# Gimbal-Motor-PowerBoard.net
KiCad netlist of a schematic drawn in EAGLE
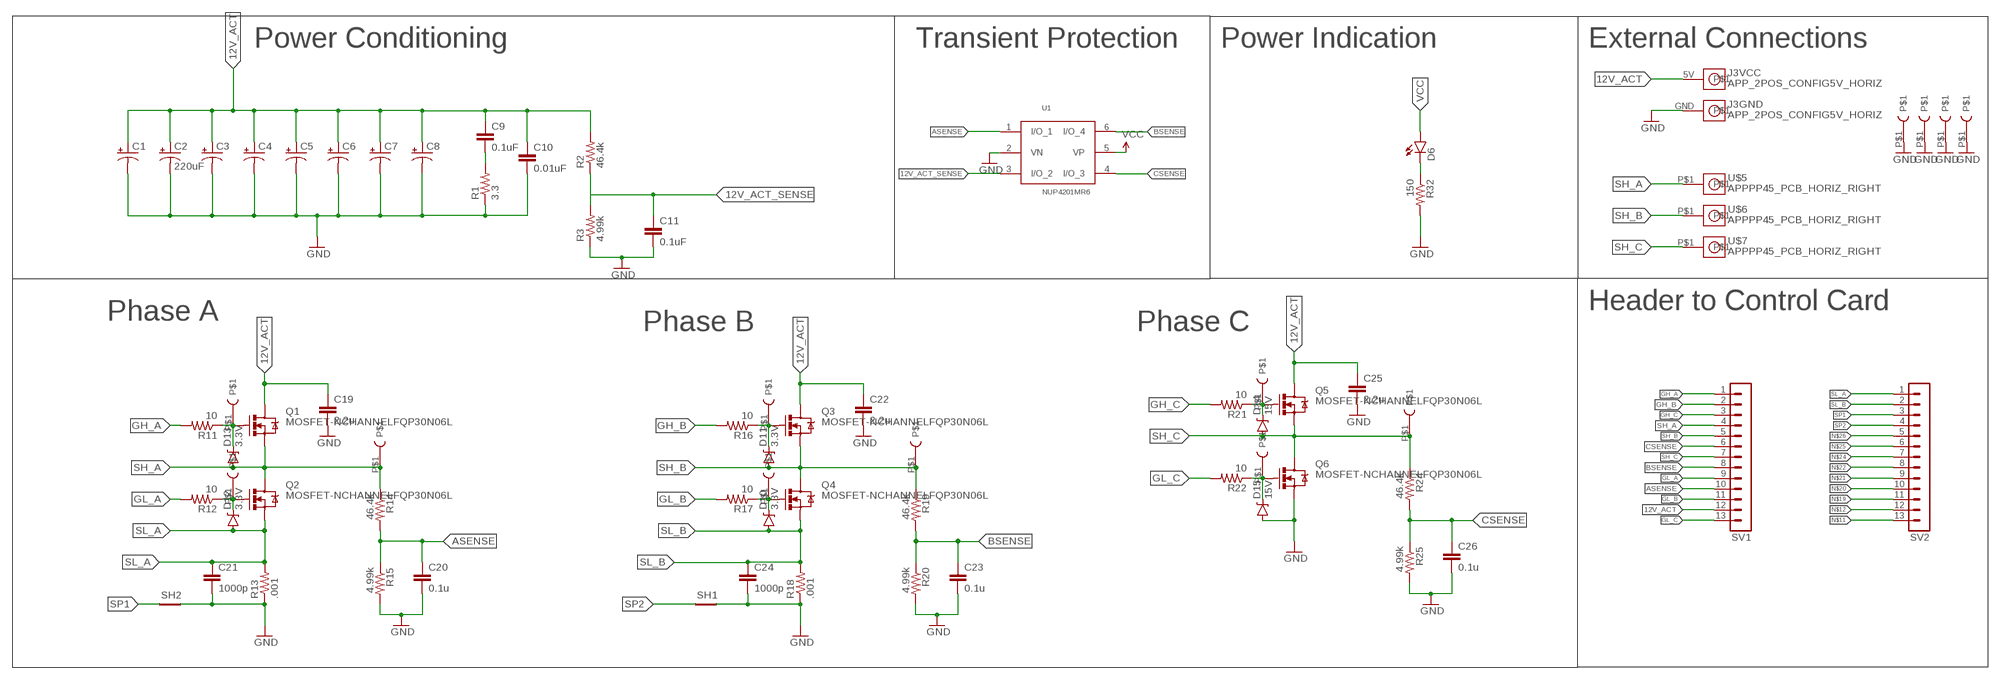
[diagram p0: schematic, sheet 1]

(export (version "E")
  (design (tool "Eeschema 10.0.6"))
  (components
    (comp (ref "C1")
      (value "CAP_POLPTH4")
      (footprint "eagle-import:CPOL-RADIAL-1000UF-25V")
      (libsource (lib "eagle-import") (part "CAP_POLPTH4"))
    )
    (comp (ref "C2")
      (value "220uF")
      (footprint "eagle-import:CPOL-RADIAL-1000UF-25V")
      (libsource (lib "eagle-import") (part "CAP_POLPTH4"))
    )
    (comp (ref "C3")
      (value "CAP_POLPTH4")
      (footprint "eagle-import:CPOL-RADIAL-1000UF-25V")
      (libsource (lib "eagle-import") (part "CAP_POLPTH4"))
    )
    (comp (ref "C4")
      (value "CAP_POLPTH4")
      (footprint "eagle-import:CPOL-RADIAL-1000UF-25V")
      (libsource (lib "eagle-import") (part "CAP_POLPTH4"))
    )
    (comp (ref "C5")
      (value "CAP_POLPTH4")
      (footprint "eagle-import:CPOL-RADIAL-1000UF-25V")
      (libsource (lib "eagle-import") (part "CAP_POLPTH4"))
    )
    (comp (ref "C6")
      (value "CAP_POLPTH4")
      (footprint "eagle-import:CPOL-RADIAL-1000UF-25V")
      (libsource (lib "eagle-import") (part "CAP_POLPTH4"))
    )
    (comp (ref "C7")
      (value "CAP_POLPTH4")
      (footprint "eagle-import:CPOL-RADIAL-1000UF-25V")
      (libsource (lib "eagle-import") (part "CAP_POLPTH4"))
    )
    (comp (ref "C8")
      (value "CAP_POLPTH4")
      (footprint "eagle-import:CPOL-RADIAL-1000UF-25V")
      (libsource (lib "eagle-import") (part "CAP_POLPTH4"))
    )
    (comp (ref "C9")
      (value "0.1uF")
      (footprint "eagle-import:0805")
      (libsource (lib "eagle-import") (part "CAP0805"))
    )
    (comp (ref "C10")
      (value "0.01uF")
      (footprint "eagle-import:0805")
      (libsource (lib "eagle-import") (part "CAP0805"))
    )
    (comp (ref "C11")
      (value "0.1uF")
      (footprint "eagle-import:0805")
      (libsource (lib "eagle-import") (part "CAP0805"))
    )
    (comp (ref "C19")
      (value "2.2u")
      (footprint "eagle-import:1206")
      (libsource (lib "eagle-import") (part "CAP1206"))
    )
    (comp (ref "C20")
      (value "0.1u")
      (footprint "eagle-import:0805")
      (libsource (lib "eagle-import") (part "CAP0805"))
    )
    (comp (ref "C21")
      (value "1000p")
      (footprint "eagle-import:0805")
      (libsource (lib "eagle-import") (part "CAP0805"))
    )
    (comp (ref "C22")
      (value "2.2u")
      (footprint "eagle-import:1206")
      (libsource (lib "eagle-import") (part "CAP1206"))
    )
    (comp (ref "C23")
      (value "0.1u")
      (footprint "eagle-import:0805")
      (libsource (lib "eagle-import") (part "CAP0805"))
    )
    (comp (ref "C24")
      (value "1000p")
      (footprint "eagle-import:0805")
      (libsource (lib "eagle-import") (part "CAP0805"))
    )
    (comp (ref "C25")
      (value "2.2u")
      (footprint "eagle-import:1206")
      (libsource (lib "eagle-import") (part "CAP1206"))
    )
    (comp (ref "C26")
      (value "0.1u")
      (footprint "eagle-import:0805")
      (libsource (lib "eagle-import") (part "CAP0805"))
    )
    (comp (ref "D6")
      (value "LED1206")
      (footprint "eagle-import:LED-1206")
      (libsource (lib "eagle-import") (part "LED1206"))
    )
    (comp (ref "D10")
      (value "3.3V")
      (footprint "eagle-import:SOD-323")
      (libsource (lib "eagle-import") (part "DIODE-ZENER3.3V"))
    )
    (comp (ref "D11")
      (value "3.3V")
      (footprint "eagle-import:SOD-323")
      (libsource (lib "eagle-import") (part "DIODE-ZENER3.3V"))
    )
    (comp (ref "D12")
      (value "3.3V")
      (footprint "eagle-import:SOD-323")
      (libsource (lib "eagle-import") (part "DIODE-ZENER3.3V"))
    )
    (comp (ref "D13")
      (value "3.3V")
      (footprint "eagle-import:SOD-323")
      (libsource (lib "eagle-import") (part "DIODE-ZENER3.3V"))
    )
    (comp (ref "D14")
      (value "15V")
      (footprint "eagle-import:SOD-323")
      (libsource (lib "eagle-import") (part "DIODE-ZENER3.3V"))
    )
    (comp (ref "D15")
      (value "15V")
      (footprint "eagle-import:SOD-323")
      (libsource (lib "eagle-import") (part "DIODE-ZENER3.3V"))
    )
    (comp (ref "J3")
      (value "APP_2POS_CONFIG5V_HORIZ")
      (footprint "eagle-import:APP45_5V_HORIZ_CONFIG")
      (libsource (lib "eagle-import") (part "APP_2POS_CONFIG5V_HORIZ"))
    )
    (comp (ref "Q1")
      (value "MOSFET-NCHANNELFQP30N06L")
      (footprint "eagle-import:TO220V")
      (libsource (lib "eagle-import") (part "MOSFET-NCHANNELFQP30N06L"))
    )
    (comp (ref "Q2")
      (value "MOSFET-NCHANNELFQP30N06L")
      (footprint "eagle-import:TO220V")
      (libsource (lib "eagle-import") (part "MOSFET-NCHANNELFQP30N06L"))
    )
    (comp (ref "Q3")
      (value "MOSFET-NCHANNELFQP30N06L")
      (footprint "eagle-import:TO220V")
      (libsource (lib "eagle-import") (part "MOSFET-NCHANNELFQP30N06L"))
    )
    (comp (ref "Q4")
      (value "MOSFET-NCHANNELFQP30N06L")
      (footprint "eagle-import:TO220V")
      (libsource (lib "eagle-import") (part "MOSFET-NCHANNELFQP30N06L"))
    )
    (comp (ref "Q5")
      (value "MOSFET-NCHANNELFQP30N06L")
      (footprint "eagle-import:TO220V")
      (libsource (lib "eagle-import") (part "MOSFET-NCHANNELFQP30N06L"))
    )
    (comp (ref "Q6")
      (value "MOSFET-NCHANNELFQP30N06L")
      (footprint "eagle-import:TO220V")
      (libsource (lib "eagle-import") (part "MOSFET-NCHANNELFQP30N06L"))
    )
    (comp (ref "R1")
      (value "3.3")
      (footprint "eagle-import:1206")
      (libsource (lib "eagle-import") (part "RESISTOR1206"))
    )
    (comp (ref "R2")
      (value "46.4k")
      (footprint "eagle-import:0805")
      (libsource (lib "eagle-import") (part "RESISTOR0805-RES"))
    )
    (comp (ref "R3")
      (value "4.99k")
      (footprint "eagle-import:0805")
      (libsource (lib "eagle-import") (part "RESISTOR0805-RES"))
    )
    (comp (ref "R11")
      (value "10")
      (footprint "eagle-import:0805")
      (libsource (lib "eagle-import") (part "RESISTOR0805-RES"))
    )
    (comp (ref "R12")
      (value "10")
      (footprint "eagle-import:0805")
      (libsource (lib "eagle-import") (part "RESISTOR0805-RES"))
    )
    (comp (ref "R13")
      (value ".001")
      (footprint "eagle-import:1206")
      (libsource (lib "eagle-import") (part "RESISTOR1206"))
    )
    (comp (ref "R14")
      (value "46.4k")
      (footprint "eagle-import:0805")
      (libsource (lib "eagle-import") (part "RESISTOR0805-RES"))
    )
    (comp (ref "R15")
      (value "4.99k")
      (footprint "eagle-import:0805")
      (libsource (lib "eagle-import") (part "RESISTOR0805-RES"))
    )
    (comp (ref "R16")
      (value "10")
      (footprint "eagle-import:0805")
      (libsource (lib "eagle-import") (part "RESISTOR0805-RES"))
    )
    (comp (ref "R17")
      (value "10")
      (footprint "eagle-import:0805")
      (libsource (lib "eagle-import") (part "RESISTOR0805-RES"))
    )
    (comp (ref "R18")
      (value ".001")
      (footprint "eagle-import:1206")
      (libsource (lib "eagle-import") (part "RESISTOR1206"))
    )
    (comp (ref "R19")
      (value "46.4k")
      (footprint "eagle-import:0805")
      (libsource (lib "eagle-import") (part "RESISTOR0805-RES"))
    )
    (comp (ref "R20")
      (value "4.99k")
      (footprint "eagle-import:0805")
      (libsource (lib "eagle-import") (part "RESISTOR0805-RES"))
    )
    (comp (ref "R21")
      (value "10")
      (footprint "eagle-import:0805")
      (libsource (lib "eagle-import") (part "RESISTOR0805-RES"))
    )
    (comp (ref "R22")
      (value "10")
      (footprint "eagle-import:0805")
      (libsource (lib "eagle-import") (part "RESISTOR0805-RES"))
    )
    (comp (ref "R24")
      (value "46.4k")
      (footprint "eagle-import:0805")
      (libsource (lib "eagle-import") (part "RESISTOR0805-RES"))
    )
    (comp (ref "R25")
      (value "4.99k")
      (footprint "eagle-import:0805")
      (libsource (lib "eagle-import") (part "RESISTOR0805-RES"))
    )
    (comp (ref "R32")
      (value "150")
      (footprint "eagle-import:0805")
      (libsource (lib "eagle-import") (part "RESISTOR0805-RES"))
    )
    (comp (ref "SH1")
      (value "SHORT-HT5")
      (footprint "eagle-import:SHORT_TOP-50")
      (libsource (lib "eagle-import") (part "SHORT-HT5"))
    )
    (comp (ref "SH2")
      (value "SHORT-HT5")
      (footprint "eagle-import:SHORT_TOP-50")
      (libsource (lib "eagle-import") (part "SHORT-HT5"))
    )
    (comp (ref "SV1")
      (value "MA13-1")
      (footprint "eagle-import:MA13-1")
      (libsource (lib "eagle-import") (part "MA13-1"))
    )
    (comp (ref "SV2")
      (value "MA13-1")
      (footprint "eagle-import:MA13-1")
      (libsource (lib "eagle-import") (part "MA13-1"))
    )
    (comp (ref "U$5")
      (value "APPPP45_PCB_HORIZ_RIGHT")
      (footprint "eagle-import:APP45_PCB_HORIZ_RIGHT")
      (libsource (lib "eagle-import") (part "APPPP45_PCB_HORIZ_RIGHT"))
    )
    (comp (ref "U$6")
      (value "APPPP45_PCB_HORIZ_RIGHT")
      (footprint "eagle-import:APP45_PCB_HORIZ_RIGHT")
      (libsource (lib "eagle-import") (part "APPPP45_PCB_HORIZ_RIGHT"))
    )
    (comp (ref "U$7")
      (value "APPPP45_PCB_HORIZ_RIGHT")
      (footprint "eagle-import:APP45_PCB_HORIZ_RIGHT")
      (libsource (lib "eagle-import") (part "APPPP45_PCB_HORIZ_RIGHT"))
    )
    (comp (ref "U$12")
      (value "TEST_POINT_0.1INDIAM")
      (footprint "eagle-import:TEST_POINT_0.1INDIAM")
      (libsource (lib "eagle-import") (part "TEST_POINT_0.1INDIAM"))
    )
    (comp (ref "U$15")
      (value "TEST_POINT_0.1INDIAM")
      (footprint "eagle-import:TEST_POINT_0.1INDIAM")
      (libsource (lib "eagle-import") (part "TEST_POINT_0.1INDIAM"))
    )
    (comp (ref "U$16")
      (value "TEST_POINT_0.1INDIAM")
      (footprint "eagle-import:TEST_POINT_0.1INDIAM")
      (libsource (lib "eagle-import") (part "TEST_POINT_0.1INDIAM"))
    )
    (comp (ref "U$17")
      (value "TEST_POINT_0.1INDIAM")
      (footprint "eagle-import:TEST_POINT_0.1INDIAM")
      (libsource (lib "eagle-import") (part "TEST_POINT_0.1INDIAM"))
    )
    (comp (ref "U$18")
      (value "TEST_POINT_0.1INDIAM")
      (footprint "eagle-import:TEST_POINT_0.1INDIAM")
      (libsource (lib "eagle-import") (part "TEST_POINT_0.1INDIAM"))
    )
    (comp (ref "U$19")
      (value "TEST_POINT_0.1INDIAM")
      (footprint "eagle-import:TEST_POINT_0.1INDIAM")
      (libsource (lib "eagle-import") (part "TEST_POINT_0.1INDIAM"))
    )
    (comp (ref "U$20")
      (value "TEST_POINT_0.1INDIAM")
      (footprint "eagle-import:TEST_POINT_0.1INDIAM")
      (libsource (lib "eagle-import") (part "TEST_POINT_0.1INDIAM"))
    )
    (comp (ref "U$24")
      (value "TEST_POINT_0.1INDIAM")
      (footprint "eagle-import:TEST_POINT_0.1INDIAM")
      (libsource (lib "eagle-import") (part "TEST_POINT_0.1INDIAM"))
    )
    (comp (ref "U$25")
      (value "TEST_POINT_0.1INDIAM")
      (footprint "eagle-import:TEST_POINT_0.1INDIAM")
      (libsource (lib "eagle-import") (part "TEST_POINT_0.1INDIAM"))
    )
    (comp (ref "U$26")
      (value "TEST_POINT_0.1INDIAM")
      (footprint "eagle-import:TEST_POINT_0.1INDIAM")
      (libsource (lib "eagle-import") (part "TEST_POINT_0.1INDIAM"))
    )
    (comp (ref "U$27")
      (value "TEST_POINT_0.1INDIAM")
      (footprint "eagle-import:TEST_POINT_0.1INDIAM")
      (libsource (lib "eagle-import") (part "TEST_POINT_0.1INDIAM"))
    )
    (comp (ref "U$28")
      (value "TEST_POINT_0.1INDIAM")
      (footprint "eagle-import:TEST_POINT_0.1INDIAM")
      (libsource (lib "eagle-import") (part "TEST_POINT_0.1INDIAM"))
    )
    (comp (ref "U$29")
      (value "TEST_POINT_0.1INDIAM")
      (footprint "eagle-import:TEST_POINT_0.1INDIAM")
      (libsource (lib "eagle-import") (part "TEST_POINT_0.1INDIAM"))
    )
    (comp (ref "U1")
      (value "NUP4201MR6")
      (footprint "eagle-import:TSOP-6")
      (libsource (lib "eagle-import") (part "NUP4201MR6"))
    )
  )
  (nets
    (net (code "1") (name "12V_ACT") (class "Default")
      (node (ref "C1") (pin "1") (pinfunction "+_1") (pintype "passive"))
      (node (ref "C10") (pin "1") (pinfunction "1_1") (pintype "passive"))
      (node (ref "C19") (pin "1") (pinfunction "1_1") (pintype "passive"))
      (node (ref "C2") (pin "1") (pinfunction "+_1") (pintype "passive"))
      (node (ref "C22") (pin "1") (pinfunction "1_1") (pintype "passive"))
      (node (ref "C25") (pin "1") (pinfunction "1_1") (pintype "passive"))
      (node (ref "C3") (pin "1") (pinfunction "+_1") (pintype "passive"))
      (node (ref "C4") (pin "1") (pinfunction "+_1") (pintype "passive"))
      (node (ref "C5") (pin "1") (pinfunction "+_1") (pintype "passive"))
      (node (ref "C6") (pin "1") (pinfunction "+_1") (pintype "passive"))
      (node (ref "C7") (pin "1") (pinfunction "+_1") (pintype "passive"))
      (node (ref "C8") (pin "1") (pinfunction "+_1") (pintype "passive"))
      (node (ref "C9") (pin "1") (pinfunction "1_1") (pintype "passive"))
      (node (ref "J3") (pin "5V") (pinfunction "P$1_5V") (pintype "bidirectional"))
      (node (ref "Q1") (pin "2") (pinfunction "D_2") (pintype "passive"))
      (node (ref "Q3") (pin "2") (pinfunction "D_2") (pintype "passive"))
      (node (ref "Q5") (pin "2") (pinfunction "D_2") (pintype "passive"))
      (node (ref "R2") (pin "2") (pinfunction "2_2") (pintype "passive"))
      (node (ref "SV1") (pin "12") (pinfunction "12_12") (pintype "passive"))
    )
    (net (code "2") (name "12V_ACT_SENSE") (class "Default")
      (node (ref "C11") (pin "1") (pinfunction "1_1") (pintype "passive"))
      (node (ref "R2") (pin "1") (pinfunction "1_1") (pintype "passive"))
      (node (ref "R3") (pin "2") (pinfunction "2_2") (pintype "passive"))
      (node (ref "U1") (pin "3") (pinfunction "I/O_2_3") (pintype "bidirectional"))
    )
    (net (code "3") (name "ASENSE") (class "Default")
      (node (ref "C20") (pin "1") (pinfunction "1_1") (pintype "passive"))
      (node (ref "R14") (pin "2") (pinfunction "2_2") (pintype "passive"))
      (node (ref "R15") (pin "1") (pinfunction "1_1") (pintype "passive"))
      (node (ref "SV1") (pin "10") (pinfunction "10_10") (pintype "passive"))
      (node (ref "U1") (pin "1") (pinfunction "I/O_1_1") (pintype "bidirectional"))
    )
    (net (code "4") (name "BSENSE") (class "Default")
      (node (ref "C23") (pin "1") (pinfunction "1_1") (pintype "passive"))
      (node (ref "R19") (pin "2") (pinfunction "2_2") (pintype "passive"))
      (node (ref "R20") (pin "1") (pinfunction "1_1") (pintype "passive"))
      (node (ref "SV1") (pin "8") (pinfunction "8_8") (pintype "passive"))
      (node (ref "U1") (pin "6") (pinfunction "I/O_4_6") (pintype "bidirectional"))
    )
    (net (code "5") (name "CSENSE") (class "Default")
      (node (ref "C26") (pin "1") (pinfunction "1_1") (pintype "passive"))
      (node (ref "R24") (pin "2") (pinfunction "2_2") (pintype "passive"))
      (node (ref "R25") (pin "1") (pinfunction "1_1") (pintype "passive"))
      (node (ref "SV1") (pin "6") (pinfunction "6_6") (pintype "passive"))
      (node (ref "U1") (pin "4") (pinfunction "I/O_3_4") (pintype "bidirectional"))
    )
    (net (code "6") (name "GH_A") (class "Default")
      (node (ref "R11") (pin "2") (pinfunction "2_2") (pintype "passive"))
      (node (ref "SV1") (pin "1") (pinfunction "1_1") (pintype "passive"))
    )
    (net (code "7") (name "GH_B") (class "Default")
      (node (ref "R16") (pin "2") (pinfunction "2_2") (pintype "passive"))
      (node (ref "SV1") (pin "2") (pinfunction "2_2") (pintype "passive"))
    )
    (net (code "8") (name "GH_C") (class "Default")
      (node (ref "R21") (pin "2") (pinfunction "2_2") (pintype "passive"))
      (node (ref "SV1") (pin "3") (pinfunction "3_3") (pintype "passive"))
    )
    (net (code "9") (name "GL_A") (class "Default")
      (node (ref "R12") (pin "2") (pinfunction "2_2") (pintype "passive"))
      (node (ref "SV1") (pin "9") (pinfunction "9_9") (pintype "passive"))
    )
    (net (code "10") (name "GL_B") (class "Default")
      (node (ref "R17") (pin "2") (pinfunction "2_2") (pintype "passive"))
      (node (ref "SV1") (pin "11") (pinfunction "11_11") (pintype "passive"))
    )
    (net (code "11") (name "GL_C") (class "Default")
      (node (ref "R22") (pin "2") (pinfunction "2_2") (pintype "passive"))
      (node (ref "SV1") (pin "13") (pinfunction "13_13") (pintype "passive"))
    )
    (net (code "12") (name "GND") (class "Default")
      (node (ref "C1") (pin "2") (pinfunction "-_2") (pintype "passive"))
      (node (ref "C10") (pin "2") (pinfunction "2_2") (pintype "passive"))
      (node (ref "C11") (pin "2") (pinfunction "2_2") (pintype "passive"))
      (node (ref "C19") (pin "2") (pinfunction "2_2") (pintype "passive"))
      (node (ref "C2") (pin "2") (pinfunction "-_2") (pintype "passive"))
      (node (ref "C20") (pin "2") (pinfunction "2_2") (pintype "passive"))
      (node (ref "C21") (pin "2") (pinfunction "2_2") (pintype "passive"))
      (node (ref "C22") (pin "2") (pinfunction "2_2") (pintype "passive"))
      (node (ref "C23") (pin "2") (pinfunction "2_2") (pintype "passive"))
      (node (ref "C24") (pin "2") (pinfunction "2_2") (pintype "passive"))
      (node (ref "C25") (pin "2") (pinfunction "2_2") (pintype "passive"))
      (node (ref "C26") (pin "2") (pinfunction "2_2") (pintype "passive"))
      (node (ref "C3") (pin "2") (pinfunction "-_2") (pintype "passive"))
      (node (ref "C4") (pin "2") (pinfunction "-_2") (pintype "passive"))
      (node (ref "C5") (pin "2") (pinfunction "-_2") (pintype "passive"))
      (node (ref "C6") (pin "2") (pinfunction "-_2") (pintype "passive"))
      (node (ref "C7") (pin "2") (pinfunction "-_2") (pintype "passive"))
      (node (ref "C8") (pin "2") (pinfunction "-_2") (pintype "passive"))
      (node (ref "D15") (pin "A") (pinfunction "A_A") (pintype "passive"))
      (node (ref "J3") (pin "GND") (pinfunction "P$1_GND") (pintype "bidirectional"))
      (node (ref "Q6") (pin "3") (pinfunction "S_3") (pintype "passive"))
      (node (ref "R1") (pin "1") (pinfunction "1_1") (pintype "passive"))
      (node (ref "R13") (pin "1") (pinfunction "1_1") (pintype "passive"))
      (node (ref "R15") (pin "2") (pinfunction "2_2") (pintype "passive"))
      (node (ref "R18") (pin "1") (pinfunction "1_1") (pintype "passive"))
      (node (ref "R20") (pin "2") (pinfunction "2_2") (pintype "passive"))
      (node (ref "R25") (pin "2") (pinfunction "2_2") (pintype "passive"))
      (node (ref "R3") (pin "1") (pinfunction "1_1") (pintype "passive"))
      (node (ref "R32") (pin "2") (pinfunction "2_2") (pintype "passive"))
      (node (ref "SH1") (pin "2") (pinfunction "P$2_2") (pintype "bidirectional"))
      (node (ref "SH2") (pin "2") (pinfunction "P$2_2") (pintype "bidirectional"))
      (node (ref "U$26") (pin "P$1") (pinfunction "P$1_P$1") (pintype "bidirectional"))
      (node (ref "U$27") (pin "P$1") (pinfunction "P$1_P$1") (pintype "bidirectional"))
      (node (ref "U$28") (pin "P$1") (pinfunction "P$1_P$1") (pintype "bidirectional"))
      (node (ref "U$29") (pin "P$1") (pinfunction "P$1_P$1") (pintype "bidirectional"))
      (node (ref "U1") (pin "2") (pinfunction "VN_2") (pintype "bidirectional"))
    )
    (net (code "13") (name "N$11") (class "Default")
      (node (ref "SV2") (pin "13") (pinfunction "13_13") (pintype "passive"))
    )
    (net (code "14") (name "N$12") (class "Default")
      (node (ref "SV2") (pin "12") (pinfunction "12_12") (pintype "passive"))
    )
    (net (code "15") (name "N$19") (class "Default")
      (node (ref "SV2") (pin "11") (pinfunction "11_11") (pintype "passive"))
    )
    (net (code "16") (name "N$20") (class "Default")
      (node (ref "SV2") (pin "10") (pinfunction "10_10") (pintype "passive"))
    )
    (net (code "17") (name "N$21") (class "Default")
      (node (ref "SV2") (pin "9") (pinfunction "9_9") (pintype "passive"))
    )
    (net (code "18") (name "N$22") (class "Default")
      (node (ref "SV2") (pin "8") (pinfunction "8_8") (pintype "passive"))
    )
    (net (code "19") (name "N$24") (class "Default")
      (node (ref "SV2") (pin "7") (pinfunction "7_7") (pintype "passive"))
    )
    (net (code "20") (name "N$25") (class "Default")
      (node (ref "SV2") (pin "6") (pinfunction "6_6") (pintype "passive"))
    )
    (net (code "21") (name "N$26") (class "Default")
      (node (ref "SV2") (pin "5") (pinfunction "5_5") (pintype "passive"))
    )
    (net (code "22") (name "Net-(C9-Pad2)") (class "Default")
      (node (ref "C9") (pin "2") (pinfunction "2_2") (pintype "passive"))
      (node (ref "R1") (pin "2") (pinfunction "2_2") (pintype "passive"))
    )
    (net (code "23") (name "Net-(D6-PadC)") (class "Default")
      (node (ref "D6") (pin "C") (pinfunction "C_C") (pintype "passive"))
      (node (ref "R32") (pin "1") (pinfunction "1_1") (pintype "passive"))
    )
    (net (code "24") (name "Net-(Q1-G)") (class "Default")
      (node (ref "D13") (pin "C") (pinfunction "C_C") (pintype "passive"))
      (node (ref "Q1") (pin "1") (pinfunction "G_1") (pintype "passive"))
      (node (ref "R11") (pin "1") (pinfunction "1_1") (pintype "passive"))
      (node (ref "U$12") (pin "P$1") (pinfunction "P$1_P$1") (pintype "bidirectional"))
    )
    (net (code "25") (name "Net-(Q2-G)") (class "Default")
      (node (ref "D12") (pin "C") (pinfunction "C_C") (pintype "passive"))
      (node (ref "Q2") (pin "1") (pinfunction "G_1") (pintype "passive"))
      (node (ref "R12") (pin "1") (pinfunction "1_1") (pintype "passive"))
      (node (ref "U$15") (pin "P$1") (pinfunction "P$1_P$1") (pintype "bidirectional"))
    )
    (net (code "26") (name "Net-(Q3-G)") (class "Default")
      (node (ref "D11") (pin "C") (pinfunction "C_C") (pintype "passive"))
      (node (ref "Q3") (pin "1") (pinfunction "G_1") (pintype "passive"))
      (node (ref "R16") (pin "1") (pinfunction "1_1") (pintype "passive"))
      (node (ref "U$16") (pin "P$1") (pinfunction "P$1_P$1") (pintype "bidirectional"))
    )
    (net (code "27") (name "Net-(Q4-G)") (class "Default")
      (node (ref "D10") (pin "C") (pinfunction "C_C") (pintype "passive"))
      (node (ref "Q4") (pin "1") (pinfunction "G_1") (pintype "passive"))
      (node (ref "R17") (pin "1") (pinfunction "1_1") (pintype "passive"))
      (node (ref "U$17") (pin "P$1") (pinfunction "P$1_P$1") (pintype "bidirectional"))
    )
    (net (code "28") (name "Net-(Q5-G)") (class "Default")
      (node (ref "D14") (pin "C") (pinfunction "C_C") (pintype "passive"))
      (node (ref "Q5") (pin "1") (pinfunction "G_1") (pintype "passive"))
      (node (ref "R21") (pin "1") (pinfunction "1_1") (pintype "passive"))
      (node (ref "U$18") (pin "P$1") (pinfunction "P$1_P$1") (pintype "bidirectional"))
    )
    (net (code "29") (name "Net-(Q6-G)") (class "Default")
      (node (ref "D15") (pin "C") (pinfunction "C_C") (pintype "passive"))
      (node (ref "Q6") (pin "1") (pinfunction "G_1") (pintype "passive"))
      (node (ref "R22") (pin "1") (pinfunction "1_1") (pintype "passive"))
      (node (ref "U$19") (pin "P$1") (pinfunction "P$1_P$1") (pintype "bidirectional"))
    )
    (net (code "30") (name "SH_A") (class "Default")
      (node (ref "D13") (pin "A") (pinfunction "A_A") (pintype "passive"))
      (node (ref "Q1") (pin "3") (pinfunction "S_3") (pintype "passive"))
      (node (ref "Q2") (pin "2") (pinfunction "D_2") (pintype "passive"))
      (node (ref "R14") (pin "1") (pinfunction "1_1") (pintype "passive"))
      (node (ref "SV1") (pin "4") (pinfunction "4_4") (pintype "passive"))
      (node (ref "U$25") (pin "P$1") (pinfunction "P$1_P$1") (pintype "bidirectional"))
      (node (ref "U$5") (pin "P$1") (pinfunction "P$1_P$1") (pintype "bidirectional"))
    )
    (net (code "31") (name "SH_B") (class "Default")
      (node (ref "D11") (pin "A") (pinfunction "A_A") (pintype "passive"))
      (node (ref "Q3") (pin "3") (pinfunction "S_3") (pintype "passive"))
      (node (ref "Q4") (pin "2") (pinfunction "D_2") (pintype "passive"))
      (node (ref "R19") (pin "1") (pinfunction "1_1") (pintype "passive"))
      (node (ref "SV1") (pin "5") (pinfunction "5_5") (pintype "passive"))
      (node (ref "U$24") (pin "P$1") (pinfunction "P$1_P$1") (pintype "bidirectional"))
      (node (ref "U$6") (pin "P$1") (pinfunction "P$1_P$1") (pintype "bidirectional"))
    )
    (net (code "32") (name "SH_C") (class "Default")
      (node (ref "D14") (pin "A") (pinfunction "A_A") (pintype "passive"))
      (node (ref "Q5") (pin "3") (pinfunction "S_3") (pintype "passive"))
      (node (ref "Q6") (pin "2") (pinfunction "D_2") (pintype "passive"))
      (node (ref "R24") (pin "1") (pinfunction "1_1") (pintype "passive"))
      (node (ref "SV1") (pin "7") (pinfunction "7_7") (pintype "passive"))
      (node (ref "U$20") (pin "P$1") (pinfunction "P$1_P$1") (pintype "bidirectional"))
      (node (ref "U$7") (pin "P$1") (pinfunction "P$1_P$1") (pintype "bidirectional"))
    )
    (net (code "33") (name "SL_A") (class "Default")
      (node (ref "C21") (pin "1") (pinfunction "1_1") (pintype "passive"))
      (node (ref "D12") (pin "A") (pinfunction "A_A") (pintype "passive"))
      (node (ref "Q2") (pin "3") (pinfunction "S_3") (pintype "passive"))
      (node (ref "R13") (pin "2") (pinfunction "2_2") (pintype "passive"))
      (node (ref "SV2") (pin "1") (pinfunction "1_1") (pintype "passive"))
    )
    (net (code "34") (name "SL_B") (class "Default")
      (node (ref "C24") (pin "1") (pinfunction "1_1") (pintype "passive"))
      (node (ref "D10") (pin "A") (pinfunction "A_A") (pintype "passive"))
      (node (ref "Q4") (pin "3") (pinfunction "S_3") (pintype "passive"))
      (node (ref "R18") (pin "2") (pinfunction "2_2") (pintype "passive"))
      (node (ref "SV2") (pin "2") (pinfunction "2_2") (pintype "passive"))
    )
    (net (code "35") (name "SP1") (class "Default")
      (node (ref "SH2") (pin "1") (pinfunction "P$1_1") (pintype "bidirectional"))
      (node (ref "SV2") (pin "3") (pinfunction "3_3") (pintype "passive"))
    )
    (net (code "36") (name "SP2") (class "Default")
      (node (ref "SH1") (pin "1") (pinfunction "P$1_1") (pintype "bidirectional"))
      (node (ref "SV2") (pin "4") (pinfunction "4_4") (pintype "passive"))
    )
    (net (code "37") (name "VCC") (class "Default")
      (node (ref "D6") (pin "A") (pinfunction "A_A") (pintype "passive"))
      (node (ref "U1") (pin "5") (pinfunction "VP_5") (pintype "bidirectional"))
    )
  )
)
